# EPRTwinkie.net
KiCad netlist of a schematic drawn in Altium Designer
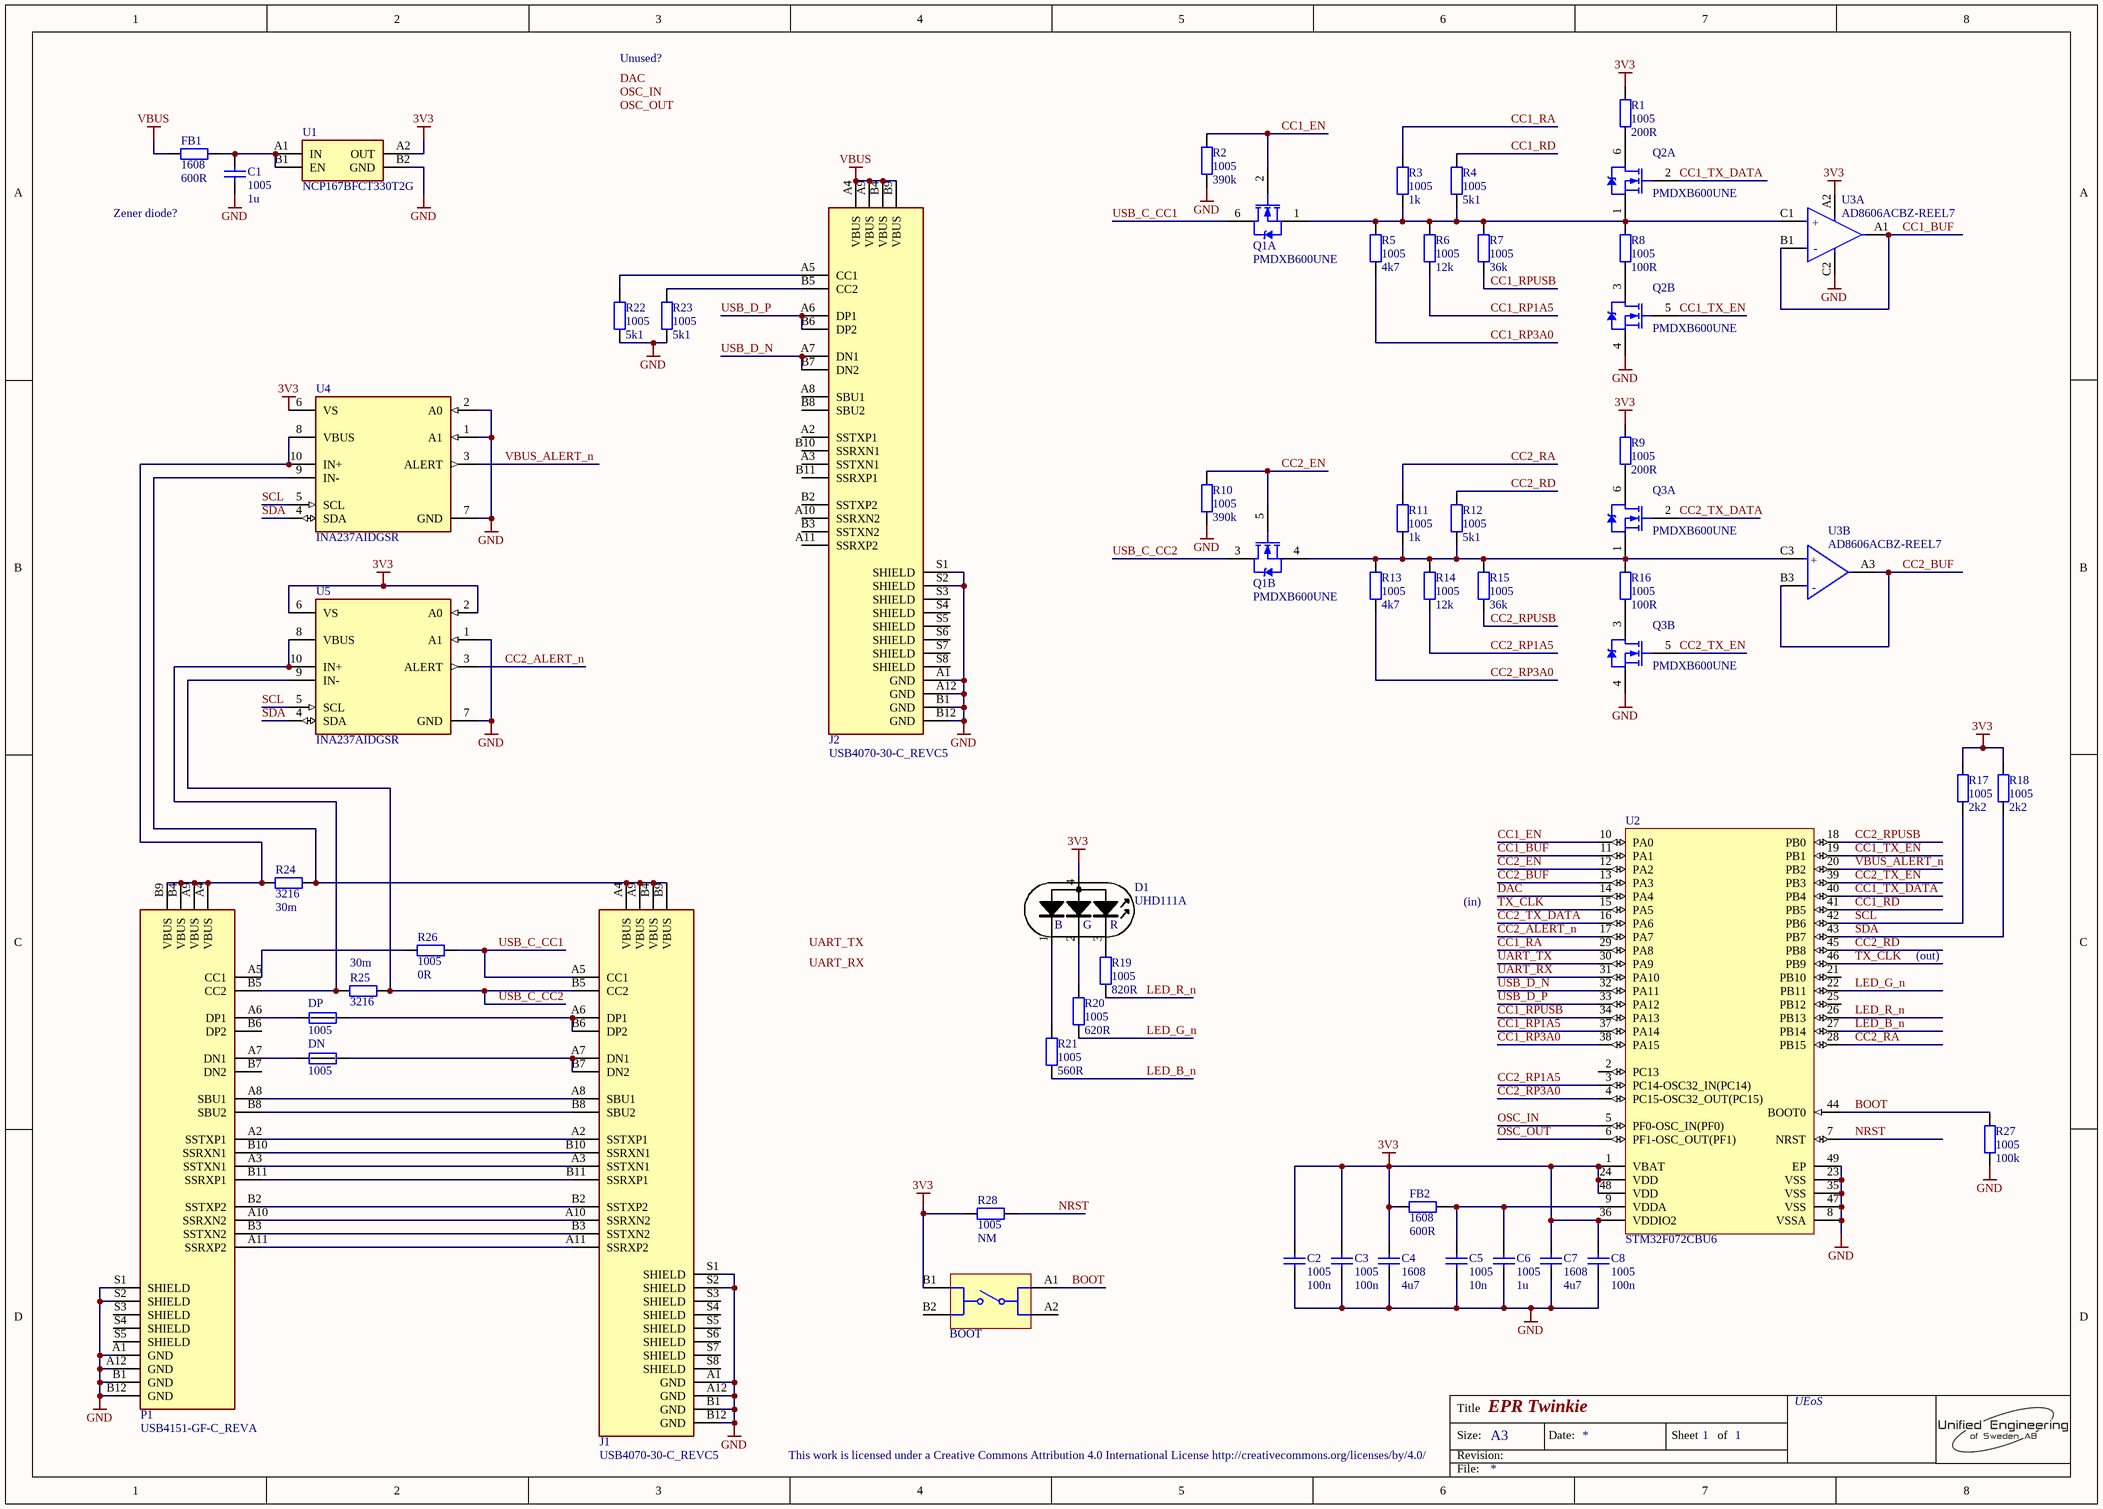
[diagram p0: EPRTwinkie.SchDoc]

(export (version "E")
  (design (tool "Eeschema 10.0.6"))
  (components
    (comp (ref "BOOT")
      (value "434331013822")
      (footprint "434331013822")
      (description "WS-TASU SMT Tact Switch 3.5x2.9mm side push, SPST-NO, 12VDC, 50mA, 220g")
      (fields (field (name "MANUFACTURER") "Wurth Elektronik"))
      (libsource (lib "Altium_WS-TASU (rev22a)") (part "434331013822"))
    )
    (comp (ref "C1")
      (value "1005")
      (footprint "CAPC1005")
      (description "Capacitor")
      (fields (field (name "ALTIUM_VALUE") "1u") (field (name "PUBLISHER") "Altium Limited"))
      (libsource (lib "Miscellaneous Devices") (part "Cap"))
    )
    (comp (ref "C2")
      (value "1005")
      (footprint "CAPC1005")
      (description "Capacitor")
      (fields (field (name "ALTIUM_VALUE") "100n") (field (name "PUBLISHER") "Altium Limited"))
      (libsource (lib "Miscellaneous Devices") (part "Cap"))
    )
    (comp (ref "C3")
      (value "1005")
      (footprint "CAPC1005")
      (description "Capacitor")
      (fields (field (name "ALTIUM_VALUE") "100n") (field (name "PUBLISHER") "Altium Limited"))
      (libsource (lib "Miscellaneous Devices") (part "Cap"))
    )
    (comp (ref "C4")
      (value "1608")
      (footprint "CAPC1608")
      (description "Capacitor")
      (fields (field (name "ALTIUM_VALUE") "4u7") (field (name "PUBLISHER") "Altium Limited"))
      (libsource (lib "Miscellaneous Devices") (part "Cap"))
    )
    (comp (ref "C5")
      (value "1005")
      (footprint "CAPC1005")
      (description "Capacitor")
      (fields (field (name "ALTIUM_VALUE") "10n") (field (name "PUBLISHER") "Altium Limited"))
      (libsource (lib "Miscellaneous Devices") (part "Cap"))
    )
    (comp (ref "C6")
      (value "1005")
      (footprint "CAPC1005")
      (description "Capacitor")
      (fields (field (name "ALTIUM_VALUE") "1u") (field (name "PUBLISHER") "Altium Limited"))
      (libsource (lib "Miscellaneous Devices") (part "Cap"))
    )
    (comp (ref "C7")
      (value "1608")
      (footprint "CAPC1608")
      (description "Capacitor")
      (fields (field (name "ALTIUM_VALUE") "4u7") (field (name "PUBLISHER") "Altium Limited"))
      (libsource (lib "Miscellaneous Devices") (part "Cap"))
    )
    (comp (ref "C8")
      (value "1005")
      (footprint "CAPC1005")
      (description "Capacitor")
      (fields (field (name "ALTIUM_VALUE") "100n") (field (name "PUBLISHER") "Altium Limited"))
      (libsource (lib "Miscellaneous Devices") (part "Cap"))
    )
    (comp (ref "D1")
      (value "UHD111A")
      (footprint "Cree UHD111A")
      (description "LED RGB SMD")
      (libsource (lib "UHD111A_LED") (part "UHD111A_LED"))
    )
    (comp (ref "DN")
      (value "1005")
      (footprint "DogBone1005")
      (libsource (lib "dogbone") (part "DogBone1005"))
    )
    (comp (ref "DP")
      (value "1005")
      (footprint "DogBone1005")
      (libsource (lib "dogbone") (part "DogBone1005"))
    )
    (comp (ref "FB1")
      (value "1608")
      (footprint "RESC1608")
      (description "Resistor")
      (fields (field (name "ALTIUM_VALUE") "600R") (field (name "PUBLISHER") "Altium Limited"))
      (libsource (lib "") (part "Res2_2"))
    )
    (comp (ref "FB2")
      (value "1608")
      (footprint "RESC1608")
      (description "Resistor")
      (fields (field (name "ALTIUM_VALUE") "600R") (field (name "PUBLISHER") "Altium Limited"))
      (libsource (lib "") (part "Res2_2"))
    )
    (comp (ref "J1")
      (value "USB4070-30-C_REVC5")
      (footprint "GCT_USB4070-30-C_Straddle")
      (fields
        (field (name "DIGI-KEY_PART_NUMBER") "2073-USB4070-30-CTR-ND")
        (field (name "MF") "Global Connector Technology")
        (field (name "MP") "USB4070-30-C")
      )
      (libsource (lib "USB4070-30-C_REVC5") (part "USB4070-30-C_REVC5"))
    )
    (comp (ref "J2")
      (value "USB4070-30-C_REVC5")
      (footprint "GCT_USB4070-30-C_Straddle")
      (fields
        (field (name "DIGI-KEY_PART_NUMBER") "2073-USB4070-30-CTR-ND")
        (field (name "MF") "Global Connector Technology")
        (field (name "MP") "USB4070-30-C")
      )
      (libsource (lib "USB4070-30-C_REVC5") (part "USB4070-30-C_REVC5"))
    )
    (comp (ref "P1")
      (value "USB4151-GF-C_REVA")
      (footprint "GCT_USB4151-GF-C_STRADDLE")
      (description "USB Type C Plug, Vertical, SMT")
      (libsource (lib "USB4151-GF-C_REVA") (part "USB4151-GF-C_REVA"))
    )
    (comp (ref "Q1")
      (value "PMDXB600UNE")
      (footprint "SON35P100X40-6N")
      (description "Dual N Channel Field Effect Transistor")
      (libsource (lib "PMDXB600UNE") (part "PMDXB600UNE"))
    )
    (comp (ref "Q2")
      (value "PMDXB600UNE")
      (footprint "SON35P100X40-6N")
      (description "Dual N Channel Field Effect Transistor")
      (libsource (lib "PMDXB600UNE") (part "PMDXB600UNE"))
    )
    (comp (ref "Q3")
      (value "PMDXB600UNE")
      (footprint "SON35P100X40-6N")
      (description "Dual N Channel Field Effect Transistor")
      (libsource (lib "PMDXB600UNE") (part "PMDXB600UNE"))
    )
    (comp (ref "R1")
      (value "1005")
      (footprint "RESC1005")
      (description "Resistor")
      (fields (field (name "ALTIUM_VALUE") "200R") (field (name "PUBLISHER") "Altium Limited"))
      (libsource (lib "Miscellaneous Devices") (part "Res2"))
    )
    (comp (ref "R2")
      (value "1005")
      (footprint "RESC1005")
      (description "Resistor")
      (fields (field (name "ALTIUM_VALUE") "390k") (field (name "PUBLISHER") "Altium Limited"))
      (libsource (lib "Miscellaneous Devices") (part "Res2"))
    )
    (comp (ref "R3")
      (value "1005")
      (footprint "RESC1005")
      (description "Resistor")
      (fields (field (name "ALTIUM_VALUE") "1k") (field (name "PUBLISHER") "Altium Limited"))
      (libsource (lib "Miscellaneous Devices") (part "Res2"))
    )
    (comp (ref "R4")
      (value "1005")
      (footprint "RESC1005")
      (description "Resistor")
      (fields (field (name "ALTIUM_VALUE") "5k1") (field (name "PUBLISHER") "Altium Limited"))
      (libsource (lib "Miscellaneous Devices") (part "Res2"))
    )
    (comp (ref "R5")
      (value "1005")
      (footprint "RESC1005")
      (description "Resistor")
      (fields (field (name "ALTIUM_VALUE") "4k7") (field (name "PUBLISHER") "Altium Limited"))
      (libsource (lib "Miscellaneous Devices") (part "Res2"))
    )
    (comp (ref "R6")
      (value "1005")
      (footprint "RESC1005")
      (description "Resistor")
      (fields (field (name "ALTIUM_VALUE") "12k") (field (name "PUBLISHER") "Altium Limited"))
      (libsource (lib "Miscellaneous Devices") (part "Res2"))
    )
    (comp (ref "R7")
      (value "1005")
      (footprint "RESC1005")
      (description "Resistor")
      (fields (field (name "ALTIUM_VALUE") "36k") (field (name "PUBLISHER") "Altium Limited"))
      (libsource (lib "Miscellaneous Devices") (part "Res2"))
    )
    (comp (ref "R8")
      (value "1005")
      (footprint "RESC1005")
      (description "Resistor")
      (fields (field (name "ALTIUM_VALUE") "100R") (field (name "PUBLISHER") "Altium Limited"))
      (libsource (lib "Miscellaneous Devices") (part "Res2"))
    )
    (comp (ref "R9")
      (value "1005")
      (footprint "RESC1005")
      (description "Resistor")
      (fields (field (name "ALTIUM_VALUE") "200R") (field (name "PUBLISHER") "Altium Limited"))
      (libsource (lib "Miscellaneous Devices") (part "Res2"))
    )
    (comp (ref "R10")
      (value "1005")
      (footprint "RESC1005")
      (description "Resistor")
      (fields (field (name "ALTIUM_VALUE") "390k") (field (name "PUBLISHER") "Altium Limited"))
      (libsource (lib "Miscellaneous Devices") (part "Res2"))
    )
    (comp (ref "R11")
      (value "1005")
      (footprint "RESC1005")
      (description "Resistor")
      (fields (field (name "ALTIUM_VALUE") "1k") (field (name "PUBLISHER") "Altium Limited"))
      (libsource (lib "Miscellaneous Devices") (part "Res2"))
    )
    (comp (ref "R12")
      (value "1005")
      (footprint "RESC1005")
      (description "Resistor")
      (fields (field (name "ALTIUM_VALUE") "5k1") (field (name "PUBLISHER") "Altium Limited"))
      (libsource (lib "Miscellaneous Devices") (part "Res2"))
    )
    (comp (ref "R13")
      (value "1005")
      (footprint "RESC1005")
      (description "Resistor")
      (fields (field (name "ALTIUM_VALUE") "4k7") (field (name "PUBLISHER") "Altium Limited"))
      (libsource (lib "Miscellaneous Devices") (part "Res2"))
    )
    (comp (ref "R14")
      (value "1005")
      (footprint "RESC1005")
      (description "Resistor")
      (fields (field (name "ALTIUM_VALUE") "12k") (field (name "PUBLISHER") "Altium Limited"))
      (libsource (lib "Miscellaneous Devices") (part "Res2"))
    )
    (comp (ref "R15")
      (value "1005")
      (footprint "RESC1005")
      (description "Resistor")
      (fields (field (name "ALTIUM_VALUE") "36k") (field (name "PUBLISHER") "Altium Limited"))
      (libsource (lib "Miscellaneous Devices") (part "Res2"))
    )
    (comp (ref "R16")
      (value "1005")
      (footprint "RESC1005")
      (description "Resistor")
      (fields (field (name "ALTIUM_VALUE") "100R") (field (name "PUBLISHER") "Altium Limited"))
      (libsource (lib "Miscellaneous Devices") (part "Res2"))
    )
    (comp (ref "R17")
      (value "1005")
      (footprint "RESC1005")
      (description "Resistor")
      (fields (field (name "ALTIUM_VALUE") "2k2") (field (name "PUBLISHER") "Altium Limited"))
      (libsource (lib "Miscellaneous Devices") (part "Res2"))
    )
    (comp (ref "R18")
      (value "1005")
      (footprint "RESC1005")
      (description "Resistor")
      (fields (field (name "ALTIUM_VALUE") "2k2") (field (name "PUBLISHER") "Altium Limited"))
      (libsource (lib "") (part "Res2_3"))
    )
    (comp (ref "R19")
      (value "1005")
      (footprint "RESC1005")
      (description "Resistor")
      (fields (field (name "ALTIUM_VALUE") "820R") (field (name "PUBLISHER") "Altium Limited"))
      (libsource (lib "Miscellaneous Devices") (part "Res2"))
    )
    (comp (ref "R20")
      (value "1005")
      (footprint "RESC1005")
      (description "Resistor")
      (fields (field (name "ALTIUM_VALUE") "620R") (field (name "PUBLISHER") "Altium Limited"))
      (libsource (lib "Miscellaneous Devices") (part "Res2"))
    )
    (comp (ref "R21")
      (value "1005")
      (footprint "RESC1005")
      (description "Resistor")
      (fields (field (name "ALTIUM_VALUE") "560R") (field (name "PUBLISHER") "Altium Limited"))
      (libsource (lib "Miscellaneous Devices") (part "Res2"))
    )
    (comp (ref "R22")
      (value "1005")
      (footprint "RESC1005")
      (description "Resistor")
      (fields (field (name "ALTIUM_VALUE") "5k1") (field (name "PUBLISHER") "Altium Limited"))
      (libsource (lib "Miscellaneous Devices") (part "Res2"))
    )
    (comp (ref "R23")
      (value "1005")
      (footprint "RESC1005")
      (description "Resistor")
      (fields (field (name "ALTIUM_VALUE") "5k1") (field (name "PUBLISHER") "Altium Limited"))
      (libsource (lib "Miscellaneous Devices") (part "Res2"))
    )
    (comp (ref "R24")
      (value "3216")
      (footprint "RESC3216")
      (description "Resistor")
      (fields (field (name "ALTIUM_VALUE") "30m") (field (name "PUBLISHER") "Altium Limited"))
      (libsource (lib "") (part "Res2_1"))
    )
    (comp (ref "R25")
      (value "3216")
      (footprint "RESC3216")
      (description "Resistor")
      (fields (field (name "ALTIUM_VALUE") "30m") (field (name "PUBLISHER") "Altium Limited"))
      (libsource (lib "") (part "Res2_1"))
    )
    (comp (ref "R26")
      (value "1005")
      (footprint "RESC1005")
      (description "Resistor")
      (fields (field (name "ALTIUM_VALUE") "0R") (field (name "PUBLISHER") "Altium Limited"))
      (libsource (lib "") (part "Res2_1"))
    )
    (comp (ref "R27")
      (value "1005")
      (footprint "RESC1005")
      (description "Resistor")
      (fields (field (name "ALTIUM_VALUE") "100k") (field (name "PUBLISHER") "Altium Limited"))
      (libsource (lib "Miscellaneous Devices") (part "Res2"))
    )
    (comp (ref "R28")
      (value "1005")
      (footprint "RESC1005")
      (description "Resistor")
      (fields (field (name "ALTIUM_VALUE") "NM") (field (name "PUBLISHER") "Altium Limited"))
      (libsource (lib "") (part "Res2_1"))
    )
    (comp (ref "U1")
      (value "NCP167BFCT330T2G")
      (footprint "BGA4C35P2X2_64X64X33")
      (description "ON SEMICONDUCTOR - NCP167BFCT330T2G - LDO, FIXED, 3.3V, 0.7A, -40 TO 125DEG C")
      (fields (field (name "MOUSER PART NUMBER") "863-NCP167BFCT330T2G"))
      (libsource (lib "NCP167BFCT330T2G") (part "NCP167BFCT330T2G"))
    )
    (comp (ref "U2")
      (value "STM32F072CBU6")
      (footprint "STM-UFQFPN48_L")
      (fields (field (name "MANUFACTURER") "STMicroelectronics"))
      (libsource (lib "Altium Content Vault") (part "MC-ARM-STM32F072-UFQFPN48"))
    )
    (comp (ref "U3")
      (value "AD8606ACBZ-REEL7")
      (footprint "FP-CB-8-1-MFG")
      (description "IC OPAMP GP 2 CIRCUIT 8WLCSP")
      (libsource (lib "Altium Content Vault") (part "952876be8bf6abf80cf3d8c119ca6fa"))
    )
    (comp (ref "U4")
      (value "INA237AIDGSR")
      (footprint "FP-DGS0010A-MFG")
      (description "85-V, 16-BIT, I2C OUTPUT CURRENT")
      (libsource (lib "Altium Content Vault") (part "1b772a21bd39fa97b1474fdd4a95d16"))
    )
    (comp (ref "U5")
      (value "INA237AIDGSR")
      (footprint "FP-DGS0010A-MFG")
      (description "85-V, 16-BIT, I2C OUTPUT CURRENT")
      (libsource (lib "Altium Content Vault") (part "1b772a21bd39fa97b1474fdd4a95d16"))
    )
  )
  (nets
    (net (code "1") (name "/BOOT") (class "Default")
      (node (ref "BOOT") (pin "A1") (pinfunction "A1_A1") (pintype "passive"))
      (node (ref "R27") (pin "1") (pinfunction "1_1") (pintype "passive"))
      (node (ref "U2") (pin "44") (pinfunction "BOOT0_44") (pintype "input"))
    )
    (net (code "2") (name "/CC1_BUF") (class "Default")
      (node (ref "U2") (pin "11") (pinfunction "PA1_11") (pintype "bidirectional"))
      (node (ref "U3") (pin "A1") (pinfunction "OUTA_A1") (pintype "passive"))
      (node (ref "U3") (pin "B1") (pinfunction "-INA_B1") (pintype "tri_state"))
    )
    (net (code "3") (name "/CC1_EN") (class "Default")
      (node (ref "Q1") (pin "2") (pinfunction "G_2") (pintype "passive"))
      (node (ref "R2") (pin "1") (pinfunction "1_1") (pintype "passive"))
      (node (ref "U2") (pin "10") (pinfunction "PA0_10") (pintype "bidirectional"))
    )
    (net (code "4") (name "/CC1_RA") (class "Default")
      (node (ref "R3") (pin "1") (pinfunction "1_1") (pintype "passive"))
      (node (ref "U2") (pin "29") (pinfunction "PA8_29") (pintype "bidirectional"))
    )
    (net (code "5") (name "/CC1_RD") (class "Default")
      (node (ref "R4") (pin "1") (pinfunction "1_1") (pintype "passive"))
      (node (ref "U2") (pin "41") (pinfunction "PB5_41") (pintype "bidirectional"))
    )
    (net (code "6") (name "/CC1_RP1A5") (class "Default")
      (node (ref "R6") (pin "2") (pinfunction "2_2") (pintype "passive"))
      (node (ref "U2") (pin "37") (pinfunction "PA14_37") (pintype "bidirectional"))
    )
    (net (code "7") (name "/CC1_RP3A0") (class "Default")
      (node (ref "R5") (pin "2") (pinfunction "2_2") (pintype "passive"))
      (node (ref "U2") (pin "38") (pinfunction "PA15_38") (pintype "bidirectional"))
    )
    (net (code "8") (name "/CC1_RPUSB") (class "Default")
      (node (ref "R7") (pin "2") (pinfunction "2_2") (pintype "passive"))
      (node (ref "U2") (pin "34") (pinfunction "PA13_34") (pintype "bidirectional"))
    )
    (net (code "9") (name "/CC1_TX_DATA") (class "Default")
      (node (ref "Q2") (pin "2") (pinfunction "G_2") (pintype "passive"))
      (node (ref "U2") (pin "40") (pinfunction "PB4_40") (pintype "bidirectional"))
    )
    (net (code "10") (name "/CC1_TX_EN") (class "Default")
      (node (ref "Q2") (pin "5") (pinfunction "G_5") (pintype "passive"))
      (node (ref "U2") (pin "19") (pinfunction "PB1_19") (pintype "bidirectional"))
    )
    (net (code "11") (name "/CC2_ALERT_n") (class "Default")
      (node (ref "U2") (pin "17") (pinfunction "PA7_17") (pintype "bidirectional"))
      (node (ref "U5") (pin "3") (pinfunction "ALERT_3") (pintype "output"))
    )
    (net (code "12") (name "/CC2_BUF") (class "Default")
      (node (ref "U2") (pin "13") (pinfunction "PA3_13") (pintype "bidirectional"))
      (node (ref "U3") (pin "A3") (pinfunction "OUTB_A3") (pintype "passive"))
      (node (ref "U3") (pin "B3") (pinfunction "-INB_B3") (pintype "tri_state"))
    )
    (net (code "13") (name "/CC2_EN") (class "Default")
      (node (ref "Q1") (pin "5") (pinfunction "G_5") (pintype "passive"))
      (node (ref "R10") (pin "1") (pinfunction "1_1") (pintype "passive"))
      (node (ref "U2") (pin "12") (pinfunction "PA2_12") (pintype "bidirectional"))
    )
    (net (code "14") (name "/CC2_RA") (class "Default")
      (node (ref "R11") (pin "1") (pinfunction "1_1") (pintype "passive"))
      (node (ref "U2") (pin "28") (pinfunction "PB15_28") (pintype "bidirectional"))
    )
    (net (code "15") (name "/CC2_RD") (class "Default")
      (node (ref "R12") (pin "1") (pinfunction "1_1") (pintype "passive"))
      (node (ref "U2") (pin "45") (pinfunction "PB8_45") (pintype "bidirectional"))
    )
    (net (code "16") (name "/CC2_RP1A5") (class "Default")
      (node (ref "R14") (pin "2") (pinfunction "2_2") (pintype "passive"))
      (node (ref "U2") (pin "3") (pinfunction "PC14-OSC32_IN(PC14)_3") (pintype "bidirectional"))
    )
    (net (code "17") (name "/CC2_RP3A0") (class "Default")
      (node (ref "R13") (pin "2") (pinfunction "2_2") (pintype "passive"))
      (node (ref "U2") (pin "4") (pinfunction "PC15-OSC32_OUT(PC15)_4") (pintype "bidirectional"))
    )
    (net (code "18") (name "/CC2_RPUSB") (class "Default")
      (node (ref "R15") (pin "2") (pinfunction "2_2") (pintype "passive"))
      (node (ref "U2") (pin "18") (pinfunction "PB0_18") (pintype "bidirectional"))
    )
    (net (code "19") (name "/CC2_TX_DATA") (class "Default")
      (node (ref "Q3") (pin "2") (pinfunction "G_2") (pintype "passive"))
      (node (ref "U2") (pin "16") (pinfunction "PA6_16") (pintype "bidirectional"))
    )
    (net (code "20") (name "/CC2_TX_EN") (class "Default")
      (node (ref "Q3") (pin "5") (pinfunction "G_5") (pintype "passive"))
      (node (ref "U2") (pin "39") (pinfunction "PB3_39") (pintype "bidirectional"))
    )
    (net (code "21") (name "/DAC") (class "Default")
      (node (ref "U2") (pin "14") (pinfunction "PA4_14") (pintype "bidirectional"))
    )
    (net (code "22") (name "/LED_B_n") (class "Default")
      (node (ref "R21") (pin "2") (pinfunction "2_2") (pintype "passive"))
      (node (ref "U2") (pin "27") (pinfunction "PB14_27") (pintype "bidirectional"))
    )
    (net (code "23") (name "/LED_G_n") (class "Default")
      (node (ref "R20") (pin "2") (pinfunction "2_2") (pintype "passive"))
      (node (ref "U2") (pin "22") (pinfunction "PB11_22") (pintype "bidirectional"))
    )
    (net (code "24") (name "/LED_R_n") (class "Default")
      (node (ref "R19") (pin "2") (pinfunction "2_2") (pintype "passive"))
      (node (ref "U2") (pin "26") (pinfunction "PB13_26") (pintype "bidirectional"))
    )
    (net (code "25") (name "/NRST") (class "Default")
      (node (ref "R28") (pin "2") (pinfunction "2_2") (pintype "passive"))
      (node (ref "U2") (pin "7") (pinfunction "NRST_7") (pintype "bidirectional"))
    )
    (net (code "26") (name "/OSC_IN") (class "Default")
      (node (ref "U2") (pin "5") (pinfunction "PF0-OSC_IN(PF0)_5") (pintype "bidirectional"))
    )
    (net (code "27") (name "/OSC_OUT") (class "Default")
      (node (ref "U2") (pin "6") (pinfunction "PF1-OSC_OUT(PF1)_6") (pintype "bidirectional"))
    )
    (net (code "28") (name "/SCL") (class "Default")
      (node (ref "R17") (pin "2") (pinfunction "2_2") (pintype "passive"))
      (node (ref "U2") (pin "42") (pinfunction "PB6_42") (pintype "bidirectional"))
      (node (ref "U4") (pin "5") (pinfunction "SCL_5") (pintype "input"))
      (node (ref "U5") (pin "5") (pinfunction "SCL_5") (pintype "input"))
    )
    (net (code "29") (name "/SDA") (class "Default")
      (node (ref "R18") (pin "1") (pinfunction "1_1") (pintype "passive"))
      (node (ref "U2") (pin "43") (pinfunction "PB7_43") (pintype "bidirectional"))
      (node (ref "U4") (pin "4") (pinfunction "SDA_4") (pintype "bidirectional"))
      (node (ref "U5") (pin "4") (pinfunction "SDA_4") (pintype "bidirectional"))
    )
    (net (code "30") (name "/TX_CLK") (class "Default")
      (node (ref "U2") (pin "15") (pinfunction "PA5_15") (pintype "bidirectional"))
      (node (ref "U2") (pin "46") (pinfunction "PB9_46") (pintype "bidirectional"))
    )
    (net (code "31") (name "/UART_RX") (class "Default")
      (node (ref "U2") (pin "31") (pinfunction "PA10_31") (pintype "bidirectional"))
    )
    (net (code "32") (name "/UART_TX") (class "Default")
      (node (ref "U2") (pin "30") (pinfunction "PA9_30") (pintype "bidirectional"))
    )
    (net (code "33") (name "/USB_C_CC1") (class "Default")
      (node (ref "J1") (pin "A5") (pinfunction "CC1_A5") (pintype "passive"))
      (node (ref "Q1") (pin "6") (pinfunction "D_6") (pintype "passive"))
      (node (ref "R26") (pin "2") (pinfunction "2_2") (pintype "passive"))
    )
    (net (code "34") (name "/USB_C_CC2") (class "Default")
      (node (ref "J1") (pin "B5") (pinfunction "CC2_B5") (pintype "passive"))
      (node (ref "Q1") (pin "3") (pinfunction "D_3") (pintype "passive"))
      (node (ref "R25") (pin "2") (pinfunction "2_2") (pintype "passive"))
      (node (ref "U5") (pin "9") (pinfunction "IN-_9") (pintype "tri_state"))
    )
    (net (code "35") (name "/USB_D_N") (class "Default")
      (node (ref "J2") (pin "A7") (pinfunction "DN1_A7") (pintype "passive"))
      (node (ref "J2") (pin "B7") (pinfunction "DN2_B7") (pintype "passive"))
      (node (ref "U2") (pin "32") (pinfunction "PA11_32") (pintype "bidirectional"))
    )
    (net (code "36") (name "/USB_D_P") (class "Default")
      (node (ref "J2") (pin "A6") (pinfunction "DP1_A6") (pintype "passive"))
      (node (ref "J2") (pin "B6") (pinfunction "DP2_B6") (pintype "passive"))
      (node (ref "U2") (pin "33") (pinfunction "PA12_33") (pintype "bidirectional"))
    )
    (net (code "37") (name "/VBUS_ALERT_n") (class "Default")
      (node (ref "U2") (pin "20") (pinfunction "PB2_20") (pintype "bidirectional"))
      (node (ref "U4") (pin "3") (pinfunction "ALERT_3") (pintype "output"))
    )
    (net (code "38") (name "3V3") (class "Default")
      (node (ref "BOOT") (pin "B1") (pinfunction "B1_B1") (pintype "passive"))
      (node (ref "C2") (pin "2") (pinfunction "2_2") (pintype "passive"))
      (node (ref "C3") (pin "2") (pinfunction "2_2") (pintype "passive"))
      (node (ref "C4") (pin "2") (pinfunction "2_2") (pintype "passive"))
      (node (ref "C7") (pin "2") (pinfunction "2_2") (pintype "passive"))
      (node (ref "C8") (pin "2") (pinfunction "2_2") (pintype "passive"))
      (node (ref "D1") (pin "4") (pinfunction "C_4") (pintype "passive"))
      (node (ref "FB2") (pin "2") (pinfunction "2_2") (pintype "passive"))
      (node (ref "R1") (pin "1") (pinfunction "1_1") (pintype "passive"))
      (node (ref "R17") (pin "1") (pinfunction "1_1") (pintype "passive"))
      (node (ref "R18") (pin "2") (pinfunction "2_2") (pintype "passive"))
      (node (ref "R28") (pin "1") (pinfunction "1_1") (pintype "passive"))
      (node (ref "R9") (pin "1") (pinfunction "1_1") (pintype "passive"))
      (node (ref "U1") (pin "A2") (pinfunction "OUT_A2") (pintype "passive"))
      (node (ref "U2") (pin "1") (pinfunction "VBAT_1") (pintype "power_in"))
      (node (ref "U2") (pin "24") (pinfunction "VDD_24") (pintype "power_in"))
      (node (ref "U2") (pin "36") (pinfunction "VDDIO2_36") (pintype "power_in"))
      (node (ref "U2") (pin "48") (pinfunction "VDD_48") (pintype "power_in"))
      (node (ref "U3") (pin "A2") (pinfunction "V+_A2") (pintype "power_in"))
      (node (ref "U4") (pin "6") (pinfunction "VS_6") (pintype "power_in"))
      (node (ref "U5") (pin "2") (pinfunction "A0_2") (pintype "input"))
      (node (ref "U5") (pin "6") (pinfunction "VS_6") (pintype "power_in"))
    )
    (net (code "39") (name "GND") (class "Default")
      (node (ref "C1") (pin "1") (pinfunction "1_1") (pintype "passive"))
      (node (ref "C2") (pin "1") (pinfunction "1_1") (pintype "passive"))
      (node (ref "C3") (pin "1") (pinfunction "1_1") (pintype "passive"))
      (node (ref "C4") (pin "1") (pinfunction "1_1") (pintype "passive"))
      (node (ref "C5") (pin "1") (pinfunction "1_1") (pintype "passive"))
      (node (ref "C6") (pin "1") (pinfunction "1_1") (pintype "passive"))
      (node (ref "C7") (pin "1") (pinfunction "1_1") (pintype "passive"))
      (node (ref "C8") (pin "1") (pinfunction "1_1") (pintype "passive"))
      (node (ref "J1") (pin "A1") (pinfunction "GND_A1") (pintype "power_in"))
      (node (ref "J1") (pin "A12") (pinfunction "GND_A12") (pintype "power_in"))
      (node (ref "J1") (pin "B1") (pinfunction "GND_B1") (pintype "power_in"))
      (node (ref "J1") (pin "B12") (pinfunction "GND_B12") (pintype "power_in"))
      (node (ref "J1") (pin "S1") (pinfunction "SHIELD_S1") (pintype "passive"))
      (node (ref "J1") (pin "S2") (pinfunction "SHIELD_S2") (pintype "passive"))
      (node (ref "J2") (pin "A1") (pinfunction "GND_A1") (pintype "power_in"))
      (node (ref "J2") (pin "A12") (pinfunction "GND_A12") (pintype "power_in"))
      (node (ref "J2") (pin "B1") (pinfunction "GND_B1") (pintype "power_in"))
      (node (ref "J2") (pin "B12") (pinfunction "GND_B12") (pintype "power_in"))
      (node (ref "J2") (pin "S1") (pinfunction "SHIELD_S1") (pintype "passive"))
      (node (ref "J2") (pin "S2") (pinfunction "SHIELD_S2") (pintype "passive"))
      (node (ref "P1") (pin "A1") (pinfunction "GND_A1") (pintype "power_in"))
      (node (ref "P1") (pin "A12") (pinfunction "GND_A12") (pintype "power_in"))
      (node (ref "P1") (pin "B1") (pinfunction "GND_B1") (pintype "power_in"))
      (node (ref "P1") (pin "B12") (pinfunction "GND_B12") (pintype "power_in"))
      (node (ref "P1") (pin "S1") (pinfunction "SHIELD_S1") (pintype "passive"))
      (node (ref "P1") (pin "S2") (pinfunction "SHIELD_S2") (pintype "passive"))
      (node (ref "Q2") (pin "4") (pinfunction "S_4") (pintype "passive"))
      (node (ref "Q3") (pin "4") (pinfunction "S_4") (pintype "passive"))
      (node (ref "R10") (pin "2") (pinfunction "2_2") (pintype "passive"))
      (node (ref "R2") (pin "2") (pinfunction "2_2") (pintype "passive"))
      (node (ref "R22") (pin "2") (pinfunction "2_2") (pintype "passive"))
      (node (ref "R23") (pin "2") (pinfunction "2_2") (pintype "passive"))
      (node (ref "R27") (pin "2") (pinfunction "2_2") (pintype "passive"))
      (node (ref "U1") (pin "B2") (pinfunction "GND_B2") (pintype "passive"))
      (node (ref "U2") (pin "23") (pinfunction "VSS_23") (pintype "power_in"))
      (node (ref "U2") (pin "35") (pinfunction "VSS_35") (pintype "power_in"))
      (node (ref "U2") (pin "47") (pinfunction "VSS_47") (pintype "power_in"))
      (node (ref "U2") (pin "49") (pinfunction "EP_49") (pintype "power_in"))
      (node (ref "U2") (pin "8") (pinfunction "VSSA_8") (pintype "power_in"))
      (node (ref "U3") (pin "C2") (pinfunction "V-_C2") (pintype "power_in"))
      (node (ref "U4") (pin "1") (pinfunction "A1_1") (pintype "input"))
      (node (ref "U4") (pin "2") (pinfunction "A0_2") (pintype "input"))
      (node (ref "U4") (pin "7") (pinfunction "GND_7") (pintype "power_in"))
      (node (ref "U5") (pin "1") (pinfunction "A1_1") (pintype "input"))
      (node (ref "U5") (pin "7") (pinfunction "GND_7") (pintype "power_in"))
    )
    (net (code "40") (name "Net-(D1-Pad1)") (class "Default")
      (node (ref "D1") (pin "1") (pintype "passive"))
      (node (ref "R21") (pin "1") (pinfunction "1_1") (pintype "passive"))
    )
    (net (code "41") (name "Net-(D1-Pad2)") (class "Default")
      (node (ref "D1") (pin "2") (pintype "passive"))
      (node (ref "R20") (pin "1") (pinfunction "1_1") (pintype "passive"))
    )
    (net (code "42") (name "Net-(D1-Pad3)") (class "Default")
      (node (ref "D1") (pin "3") (pintype "passive"))
      (node (ref "R19") (pin "1") (pinfunction "1_1") (pintype "passive"))
    )
    (net (code "43") (name "Net-(DN-Net1)") (class "Default")
      (node (ref "DN") (pin "1") (pinfunction "Net1_1") (pintype "passive"))
      (node (ref "P1") (pin "A7") (pinfunction "DN1_A7") (pintype "passive"))
    )
    (net (code "44") (name "Net-(DN-Net2)") (class "Default")
      (node (ref "DN") (pin "2") (pinfunction "Net2_2") (pintype "passive"))
      (node (ref "J1") (pin "A7") (pinfunction "DN1_A7") (pintype "passive"))
      (node (ref "J1") (pin "B7") (pinfunction "DN2_B7") (pintype "passive"))
    )
    (net (code "45") (name "Net-(DP-Net1)") (class "Default")
      (node (ref "DP") (pin "1") (pinfunction "Net1_1") (pintype "passive"))
      (node (ref "P1") (pin "A6") (pinfunction "DP1_A6") (pintype "passive"))
    )
    (net (code "46") (name "Net-(DP-Net2)") (class "Default")
      (node (ref "DP") (pin "2") (pinfunction "Net2_2") (pintype "passive"))
      (node (ref "J1") (pin "A6") (pinfunction "DP1_A6") (pintype "passive"))
      (node (ref "J1") (pin "B6") (pinfunction "DP2_B6") (pintype "passive"))
    )
    (net (code "47") (name "Net-(J1-SBU1)") (class "Default")
      (node (ref "J1") (pin "A8") (pinfunction "SBU1_A8") (pintype "passive"))
      (node (ref "P1") (pin "A8") (pinfunction "SBU1_A8") (pintype "passive"))
    )
    (net (code "48") (name "Net-(J1-SBU2)") (class "Default")
      (node (ref "J1") (pin "B8") (pinfunction "SBU2_B8") (pintype "passive"))
      (node (ref "P1") (pin "B8") (pinfunction "SBU2_B8") (pintype "passive"))
    )
    (net (code "49") (name "Net-(J1-SSRXN1)") (class "Default")
      (node (ref "J1") (pin "B10") (pinfunction "SSRXN1_B10") (pintype "passive"))
      (node (ref "P1") (pin "B10") (pinfunction "SSRXN1_B10") (pintype "passive"))
    )
    (net (code "50") (name "Net-(J1-SSRXN2)") (class "Default")
      (node (ref "J1") (pin "A10") (pinfunction "SSRXN2_A10") (pintype "passive"))
      (node (ref "P1") (pin "A10") (pinfunction "SSRXN2_A10") (pintype "passive"))
    )
    (net (code "51") (name "Net-(J1-SSRXP1)") (class "Default")
      (node (ref "J1") (pin "B11") (pinfunction "SSRXP1_B11") (pintype "passive"))
      (node (ref "P1") (pin "B11") (pinfunction "SSRXP1_B11") (pintype "passive"))
    )
    (net (code "52") (name "Net-(J1-SSRXP2)") (class "Default")
      (node (ref "J1") (pin "A11") (pinfunction "SSRXP2_A11") (pintype "passive"))
      (node (ref "P1") (pin "A11") (pinfunction "SSRXP2_A11") (pintype "passive"))
    )
    (net (code "53") (name "Net-(J1-SSTXN1)") (class "Default")
      (node (ref "J1") (pin "A3") (pinfunction "SSTXN1_A3") (pintype "passive"))
      (node (ref "P1") (pin "A3") (pinfunction "SSTXN1_A3") (pintype "passive"))
    )
    (net (code "54") (name "Net-(J1-SSTXN2)") (class "Default")
      (node (ref "J1") (pin "B3") (pinfunction "SSTXN2_B3") (pintype "passive"))
      (node (ref "P1") (pin "B3") (pinfunction "SSTXN2_B3") (pintype "passive"))
    )
    (net (code "55") (name "Net-(J1-SSTXP1)") (class "Default")
      (node (ref "J1") (pin "A2") (pinfunction "SSTXP1_A2") (pintype "passive"))
      (node (ref "P1") (pin "A2") (pinfunction "SSTXP1_A2") (pintype "passive"))
    )
    (net (code "56") (name "Net-(J1-SSTXP2)") (class "Default")
      (node (ref "J1") (pin "B2") (pinfunction "SSTXP2_B2") (pintype "passive"))
      (node (ref "P1") (pin "B2") (pinfunction "SSTXP2_B2") (pintype "passive"))
    )
    (net (code "57") (name "Net-(J2-CC1)") (class "Default")
      (node (ref "J2") (pin "A5") (pinfunction "CC1_A5") (pintype "passive"))
      (node (ref "R22") (pin "1") (pinfunction "1_1") (pintype "passive"))
    )
    (net (code "58") (name "Net-(J2-CC2)") (class "Default")
      (node (ref "J2") (pin "B5") (pinfunction "CC2_B5") (pintype "passive"))
      (node (ref "R23") (pin "1") (pinfunction "1_1") (pintype "passive"))
    )
    (net (code "59") (name "Net-(P1-CC1)") (class "Default")
      (node (ref "P1") (pin "A5") (pinfunction "CC1_A5") (pintype "passive"))
      (node (ref "R26") (pin "1") (pinfunction "1_1") (pintype "passive"))
    )
    (net (code "60") (name "Net-(P1-CC2)") (class "Default")
      (node (ref "P1") (pin "B5") (pinfunction "CC2_B5") (pintype "passive"))
      (node (ref "R25") (pin "1") (pinfunction "1_1") (pintype "passive"))
      (node (ref "U5") (pin "10") (pinfunction "IN+_10") (pintype "tri_state"))
      (node (ref "U5") (pin "8") (pinfunction "VBUS_8") (pintype "power_in"))
    )
    (net (code "61") (name "Net-(Q1A-S)") (class "Default")
      (node (ref "Q1") (pin "1") (pinfunction "S_1") (pintype "passive"))
      (node (ref "Q2") (pin "1") (pinfunction "S_1") (pintype "passive"))
      (node (ref "R3") (pin "2") (pinfunction "2_2") (pintype "passive"))
      (node (ref "R4") (pin "2") (pinfunction "2_2") (pintype "passive"))
      (node (ref "R5") (pin "1") (pinfunction "1_1") (pintype "passive"))
      (node (ref "R6") (pin "1") (pinfunction "1_1") (pintype "passive"))
      (node (ref "R7") (pin "1") (pinfunction "1_1") (pintype "passive"))
      (node (ref "R8") (pin "1") (pinfunction "1_1") (pintype "passive"))
      (node (ref "U3") (pin "C1") (pinfunction "+INA_C1") (pintype "tri_state"))
    )
    (net (code "62") (name "Net-(Q1B-S)") (class "Default")
      (node (ref "Q1") (pin "4") (pinfunction "S_4") (pintype "passive"))
      (node (ref "Q3") (pin "1") (pinfunction "S_1") (pintype "passive"))
      (node (ref "R11") (pin "2") (pinfunction "2_2") (pintype "passive"))
      (node (ref "R12") (pin "2") (pinfunction "2_2") (pintype "passive"))
      (node (ref "R13") (pin "1") (pinfunction "1_1") (pintype "passive"))
      (node (ref "R14") (pin "1") (pinfunction "1_1") (pintype "passive"))
      (node (ref "R15") (pin "1") (pinfunction "1_1") (pintype "passive"))
      (node (ref "R16") (pin "1") (pinfunction "1_1") (pintype "passive"))
      (node (ref "U3") (pin "C3") (pinfunction "+INB_C3") (pintype "tri_state"))
    )
    (net (code "63") (name "Net-(Q2A-D)") (class "Default")
      (node (ref "Q2") (pin "6") (pinfunction "D_6") (pintype "passive"))
      (node (ref "R1") (pin "2") (pinfunction "2_2") (pintype "passive"))
    )
    (net (code "64") (name "Net-(Q2B-D)") (class "Default")
      (node (ref "Q2") (pin "3") (pinfunction "D_3") (pintype "passive"))
      (node (ref "R8") (pin "2") (pinfunction "2_2") (pintype "passive"))
    )
    (net (code "65") (name "Net-(Q3A-D)") (class "Default")
      (node (ref "Q3") (pin "6") (pinfunction "D_6") (pintype "passive"))
      (node (ref "R9") (pin "2") (pinfunction "2_2") (pintype "passive"))
    )
    (net (code "66") (name "Net-(Q3B-D)") (class "Default")
      (node (ref "Q3") (pin "3") (pinfunction "D_3") (pintype "passive"))
      (node (ref "R16") (pin "2") (pinfunction "2_2") (pintype "passive"))
    )
    (net (code "67") (name "Net-(U1-EN)") (class "Default")
      (node (ref "C1") (pin "2") (pinfunction "2_2") (pintype "passive"))
      (node (ref "FB1") (pin "1") (pinfunction "1_1") (pintype "passive"))
      (node (ref "U1") (pin "A1") (pinfunction "IN_A1") (pintype "passive"))
      (node (ref "U1") (pin "B1") (pinfunction "EN_B1") (pintype "passive"))
    )
    (net (code "68") (name "Net-(U2-VDDA)") (class "Default")
      (node (ref "C5") (pin "2") (pinfunction "2_2") (pintype "passive"))
      (node (ref "C6") (pin "2") (pinfunction "2_2") (pintype "passive"))
      (node (ref "FB2") (pin "1") (pinfunction "1_1") (pintype "passive"))
      (node (ref "U2") (pin "9") (pinfunction "VDDA_9") (pintype "power_in"))
    )
    (net (code "69") (name "Net-(U4-IN+)") (class "Default")
      (node (ref "P1") (pin "A4") (pinfunction "VBUS_A4") (pintype "power_in"))
      (node (ref "P1") (pin "A9") (pinfunction "VBUS_A9") (pintype "power_in"))
      (node (ref "P1") (pin "B4") (pinfunction "VBUS_B4") (pintype "power_in"))
      (node (ref "P1") (pin "B9") (pinfunction "VBUS_B9") (pintype "power_in"))
      (node (ref "R24") (pin "1") (pinfunction "1_1") (pintype "passive"))
      (node (ref "U4") (pin "10") (pinfunction "IN+_10") (pintype "tri_state"))
      (node (ref "U4") (pin "8") (pinfunction "VBUS_8") (pintype "power_in"))
    )
    (net (code "70") (name "Net-(U4-IN-)") (class "Default")
      (node (ref "J1") (pin "A4") (pinfunction "VBUS_A4") (pintype "power_in"))
      (node (ref "J1") (pin "A9") (pinfunction "VBUS_A9") (pintype "power_in"))
      (node (ref "J1") (pin "B4") (pinfunction "VBUS_B4") (pintype "power_in"))
      (node (ref "J1") (pin "B9") (pinfunction "VBUS_B9") (pintype "power_in"))
      (node (ref "R24") (pin "2") (pinfunction "2_2") (pintype "passive"))
      (node (ref "U4") (pin "9") (pinfunction "IN-_9") (pintype "tri_state"))
    )
    (net (code "71") (name "VBUS") (class "Default")
      (node (ref "FB1") (pin "2") (pinfunction "2_2") (pintype "passive"))
      (node (ref "J2") (pin "A4") (pinfunction "VBUS_A4") (pintype "power_in"))
      (node (ref "J2") (pin "A9") (pinfunction "VBUS_A9") (pintype "power_in"))
      (node (ref "J2") (pin "B4") (pinfunction "VBUS_B4") (pintype "power_in"))
      (node (ref "J2") (pin "B9") (pinfunction "VBUS_B9") (pintype "power_in"))
    )
    (net (code "72") (name "unconnected-(BOOT-PadA2)") (class "Default")
      (node (ref "BOOT") (pin "A2") (pinfunction "A2_A2") (pintype "passive"))
    )
    (net (code "73") (name "unconnected-(BOOT-PadB2)") (class "Default")
      (node (ref "BOOT") (pin "B2") (pinfunction "B2_B2") (pintype "passive"))
    )
    (net (code "74") (name "unconnected-(J1-SHIELD-PadS3)") (class "Default")
      (node (ref "J1") (pin "S3") (pinfunction "SHIELD_S3") (pintype "passive"))
    )
    (net (code "75") (name "unconnected-(J1-SHIELD-PadS4)") (class "Default")
      (node (ref "J1") (pin "S4") (pinfunction "SHIELD_S4") (pintype "passive"))
    )
    (net (code "76") (name "unconnected-(J1-SHIELD-PadS5)") (class "Default")
      (node (ref "J1") (pin "S5") (pinfunction "SHIELD_S5") (pintype "passive"))
    )
    (net (code "77") (name "unconnected-(J1-SHIELD-PadS6)") (class "Default")
      (node (ref "J1") (pin "S6") (pinfunction "SHIELD_S6") (pintype "passive"))
    )
    (net (code "78") (name "unconnected-(J1-SHIELD-PadS7)") (class "Default")
      (node (ref "J1") (pin "S7") (pinfunction "SHIELD_S7") (pintype "passive"))
    )
    (net (code "79") (name "unconnected-(J1-SHIELD-PadS8)") (class "Default")
      (node (ref "J1") (pin "S8") (pinfunction "SHIELD_S8") (pintype "passive"))
    )
    (net (code "80") (name "unconnected-(J2-SBU1-PadA8)") (class "Default")
      (node (ref "J2") (pin "A8") (pinfunction "SBU1_A8") (pintype "passive"))
    )
    (net (code "81") (name "unconnected-(J2-SBU2-PadB8)") (class "Default")
      (node (ref "J2") (pin "B8") (pinfunction "SBU2_B8") (pintype "passive"))
    )
    (net (code "82") (name "unconnected-(J2-SHIELD-PadS3)") (class "Default")
      (node (ref "J2") (pin "S3") (pinfunction "SHIELD_S3") (pintype "passive"))
    )
    (net (code "83") (name "unconnected-(J2-SHIELD-PadS4)") (class "Default")
      (node (ref "J2") (pin "S4") (pinfunction "SHIELD_S4") (pintype "passive"))
    )
    (net (code "84") (name "unconnected-(J2-SHIELD-PadS5)") (class "Default")
      (node (ref "J2") (pin "S5") (pinfunction "SHIELD_S5") (pintype "passive"))
    )
    (net (code "85") (name "unconnected-(J2-SHIELD-PadS6)") (class "Default")
      (node (ref "J2") (pin "S6") (pinfunction "SHIELD_S6") (pintype "passive"))
    )
    (net (code "86") (name "unconnected-(J2-SHIELD-PadS7)") (class "Default")
      (node (ref "J2") (pin "S7") (pinfunction "SHIELD_S7") (pintype "passive"))
    )
    (net (code "87") (name "unconnected-(J2-SHIELD-PadS8)") (class "Default")
      (node (ref "J2") (pin "S8") (pinfunction "SHIELD_S8") (pintype "passive"))
    )
    (net (code "88") (name "unconnected-(J2-SSRXN1-PadB10)") (class "Default")
      (node (ref "J2") (pin "B10") (pinfunction "SSRXN1_B10") (pintype "passive"))
    )
    (net (code "89") (name "unconnected-(J2-SSRXN2-PadA10)") (class "Default")
      (node (ref "J2") (pin "A10") (pinfunction "SSRXN2_A10") (pintype "passive"))
    )
    (net (code "90") (name "unconnected-(J2-SSRXP1-PadB11)") (class "Default")
      (node (ref "J2") (pin "B11") (pinfunction "SSRXP1_B11") (pintype "passive"))
    )
    (net (code "91") (name "unconnected-(J2-SSRXP2-PadA11)") (class "Default")
      (node (ref "J2") (pin "A11") (pinfunction "SSRXP2_A11") (pintype "passive"))
    )
    (net (code "92") (name "unconnected-(J2-SSTXN1-PadA3)") (class "Default")
      (node (ref "J2") (pin "A3") (pinfunction "SSTXN1_A3") (pintype "passive"))
    )
    (net (code "93") (name "unconnected-(J2-SSTXN2-PadB3)") (class "Default")
      (node (ref "J2") (pin "B3") (pinfunction "SSTXN2_B3") (pintype "passive"))
    )
    (net (code "94") (name "unconnected-(J2-SSTXP1-PadA2)") (class "Default")
      (node (ref "J2") (pin "A2") (pinfunction "SSTXP1_A2") (pintype "passive"))
    )
    (net (code "95") (name "unconnected-(J2-SSTXP2-PadB2)") (class "Default")
      (node (ref "J2") (pin "B2") (pinfunction "SSTXP2_B2") (pintype "passive"))
    )
    (net (code "96") (name "unconnected-(P1-DN2-PadB7)") (class "Default")
      (node (ref "P1") (pin "B7") (pinfunction "DN2_B7") (pintype "passive"))
    )
    (net (code "97") (name "unconnected-(P1-DP2-PadB6)") (class "Default")
      (node (ref "P1") (pin "B6") (pinfunction "DP2_B6") (pintype "passive"))
    )
    (net (code "98") (name "unconnected-(P1-SHIELD-PadS3)") (class "Default")
      (node (ref "P1") (pin "S3") (pinfunction "SHIELD_S3") (pintype "passive"))
    )
    (net (code "99") (name "unconnected-(P1-SHIELD-PadS4)") (class "Default")
      (node (ref "P1") (pin "S4") (pinfunction "SHIELD_S4") (pintype "passive"))
    )
    (net (code "100") (name "unconnected-(P1-SHIELD-PadS5)") (class "Default")
      (node (ref "P1") (pin "S5") (pinfunction "SHIELD_S5") (pintype "passive"))
    )
    (net (code "101") (name "unconnected-(U2-PB10-Pad21)") (class "Default")
      (node (ref "U2") (pin "21") (pinfunction "PB10_21") (pintype "bidirectional"))
    )
    (net (code "102") (name "unconnected-(U2-PB12-Pad25)") (class "Default")
      (node (ref "U2") (pin "25") (pinfunction "PB12_25") (pintype "bidirectional"))
    )
    (net (code "103") (name "unconnected-(U2-PC13-Pad2)") (class "Default")
      (node (ref "U2") (pin "2") (pinfunction "PC13_2") (pintype "bidirectional"))
    )
  )
)
